# Razz_control_board.net
KiCad netlist of a schematic drawn in EAGLE
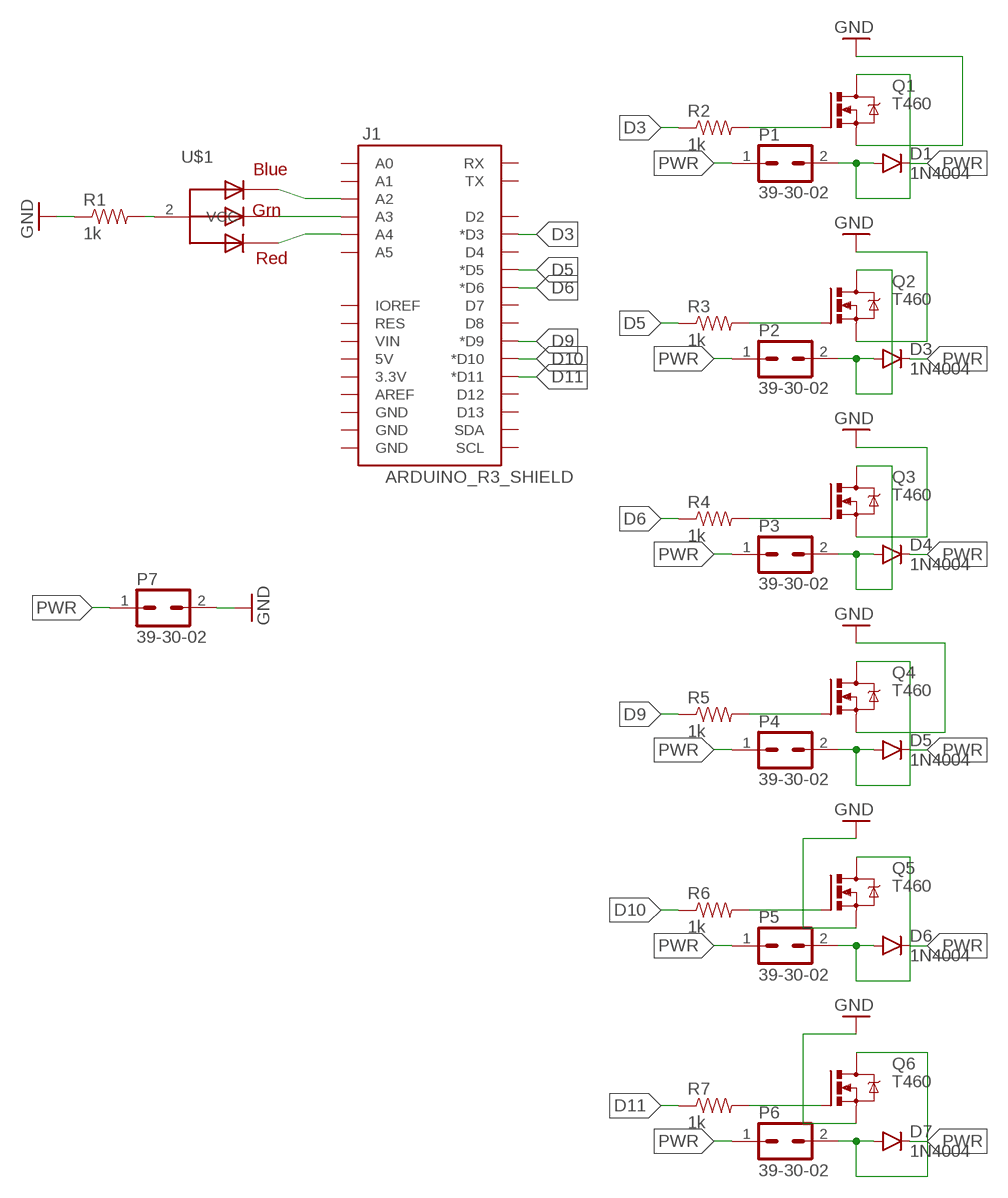
[diagram p0: schematic, sheet 1]

(export (version "E")
  (design (tool "Eeschema 10.0.6"))
  (components
    (comp (ref "D1")
      (value "1N4004")
      (footprint "eagle-import:DIODE-1N4001")
      (libsource (lib "eagle-import") (part "DIODEPTH"))
    )
    (comp (ref "D3")
      (value "1N4004")
      (footprint "eagle-import:DIODE-1N4001")
      (libsource (lib "eagle-import") (part "DIODEPTH"))
    )
    (comp (ref "D4")
      (value "1N4004")
      (footprint "eagle-import:DIODE-1N4001")
      (libsource (lib "eagle-import") (part "DIODEPTH"))
    )
    (comp (ref "D5")
      (value "1N4004")
      (footprint "eagle-import:DIODE-1N4001")
      (libsource (lib "eagle-import") (part "DIODEPTH"))
    )
    (comp (ref "D6")
      (value "1N4004")
      (footprint "eagle-import:DIODE-1N4001")
      (libsource (lib "eagle-import") (part "DIODEPTH"))
    )
    (comp (ref "D7")
      (value "1N4004")
      (footprint "eagle-import:DIODE-1N4001")
      (libsource (lib "eagle-import") (part "DIODEPTH"))
    )
    (comp (ref "J1")
      (value "ARDUINO_R3_SHIELD")
      (footprint "eagle-import:UNO_R3_SHIELD")
      (libsource (lib "eagle-import") (part "ARDUINO_R3_SHIELD"))
    )
    (comp (ref "P1")
      (value "39-30-02")
      (footprint "eagle-import:39-30-_02_")
      (libsource (lib "eagle-import") (part "39-30-?02?"))
    )
    (comp (ref "P2")
      (value "39-30-02")
      (footprint "eagle-import:39-30-_02_")
      (libsource (lib "eagle-import") (part "39-30-?02?"))
    )
    (comp (ref "P3")
      (value "39-30-02")
      (footprint "eagle-import:39-30-_02_")
      (libsource (lib "eagle-import") (part "39-30-?02?"))
    )
    (comp (ref "P4")
      (value "39-30-02")
      (footprint "eagle-import:39-30-_02_")
      (libsource (lib "eagle-import") (part "39-30-?02?"))
    )
    (comp (ref "P5")
      (value "39-30-02")
      (footprint "eagle-import:39-30-_02_")
      (libsource (lib "eagle-import") (part "39-30-?02?"))
    )
    (comp (ref "P6")
      (value "39-30-02")
      (footprint "eagle-import:39-30-_02_")
      (libsource (lib "eagle-import") (part "39-30-?02?"))
    )
    (comp (ref "P7")
      (value "39-30-02")
      (footprint "eagle-import:39-30-_02_")
      (libsource (lib "eagle-import") (part "39-30-?02?"))
    )
    (comp (ref "Q1")
      (value "T460")
      (footprint "eagle-import:TO220BV")
      (libsource (lib "eagle-import") (part "IRF540"))
    )
    (comp (ref "Q2")
      (value "T460")
      (footprint "eagle-import:TO220BV")
      (libsource (lib "eagle-import") (part "IRF540"))
    )
    (comp (ref "Q3")
      (value "T460")
      (footprint "eagle-import:TO220BV")
      (libsource (lib "eagle-import") (part "IRF540"))
    )
    (comp (ref "Q4")
      (value "T460")
      (footprint "eagle-import:TO220BV")
      (libsource (lib "eagle-import") (part "IRF540"))
    )
    (comp (ref "Q5")
      (value "T460")
      (footprint "eagle-import:TO220BV")
      (libsource (lib "eagle-import") (part "IRF540"))
    )
    (comp (ref "Q6")
      (value "T460")
      (footprint "eagle-import:TO220BV")
      (libsource (lib "eagle-import") (part "IRF540"))
    )
    (comp (ref "R1")
      (value "1k")
      (footprint "eagle-import:AXIAL-0.3EZ")
      (libsource (lib "eagle-import") (part "RESISTOREZ"))
    )
    (comp (ref "R2")
      (value "1k")
      (footprint "eagle-import:AXIAL-0.3EZ")
      (libsource (lib "eagle-import") (part "RESISTOREZ"))
    )
    (comp (ref "R3")
      (value "1k")
      (footprint "eagle-import:AXIAL-0.3EZ")
      (libsource (lib "eagle-import") (part "RESISTOREZ"))
    )
    (comp (ref "R4")
      (value "1k")
      (footprint "eagle-import:AXIAL-0.3EZ")
      (libsource (lib "eagle-import") (part "RESISTOREZ"))
    )
    (comp (ref "R5")
      (value "1k")
      (footprint "eagle-import:AXIAL-0.3EZ")
      (libsource (lib "eagle-import") (part "RESISTOREZ"))
    )
    (comp (ref "R6")
      (value "1k")
      (footprint "eagle-import:AXIAL-0.3EZ")
      (libsource (lib "eagle-import") (part "RESISTOREZ"))
    )
    (comp (ref "R7")
      (value "1k")
      (footprint "eagle-import:AXIAL-0.3EZ")
      (libsource (lib "eagle-import") (part "RESISTOREZ"))
    )
    (comp (ref "U$1")
      (value "RGBLED_CA")
      (footprint "eagle-import:LED5MMRGB")
      (libsource (lib "eagle-import") (part "RGBLED_CA"))
    )
  )
  (nets
    (net (code "1") (name "D3") (class "Default")
      (node (ref "J1") (pin "D3") (pinfunction "*D3_D3") (pintype "bidirectional"))
      (node (ref "R2") (pin "P$1") (pinfunction "1_P$1") (pintype "passive"))
    )
    (net (code "2") (name "D5") (class "Default")
      (node (ref "J1") (pin "D5") (pinfunction "*D5_D5") (pintype "bidirectional"))
      (node (ref "R3") (pin "P$1") (pinfunction "1_P$1") (pintype "passive"))
    )
    (net (code "3") (name "D6") (class "Default")
      (node (ref "J1") (pin "D6") (pinfunction "*D6_D6") (pintype "bidirectional"))
      (node (ref "R4") (pin "P$1") (pinfunction "1_P$1") (pintype "passive"))
    )
    (net (code "4") (name "D9") (class "Default")
      (node (ref "J1") (pin "D9") (pinfunction "*D9_D9") (pintype "bidirectional"))
      (node (ref "R5") (pin "P$1") (pinfunction "1_P$1") (pintype "passive"))
    )
    (net (code "5") (name "D10") (class "Default")
      (node (ref "J1") (pin "D10") (pinfunction "*D10_D10") (pintype "bidirectional"))
      (node (ref "R6") (pin "P$1") (pinfunction "1_P$1") (pintype "passive"))
    )
    (net (code "6") (name "D11") (class "Default")
      (node (ref "J1") (pin "D11") (pinfunction "*D11_D11") (pintype "bidirectional"))
      (node (ref "R7") (pin "P$1") (pinfunction "1_P$1") (pintype "passive"))
    )
    (net (code "7") (name "GND") (class "Default")
      (node (ref "P7") (pin "2") (pinfunction "2_2") (pintype "passive"))
      (node (ref "Q1") (pin "S") (pinfunction "S_S") (pintype "passive"))
      (node (ref "Q2") (pin "S") (pinfunction "S_S") (pintype "passive"))
      (node (ref "Q3") (pin "S") (pinfunction "S_S") (pintype "passive"))
      (node (ref "Q4") (pin "S") (pinfunction "S_S") (pintype "passive"))
      (node (ref "Q5") (pin "S") (pinfunction "S_S") (pintype "passive"))
      (node (ref "Q6") (pin "S") (pinfunction "S_S") (pintype "passive"))
      (node (ref "R1") (pin "P$1") (pinfunction "1_P$1") (pintype "passive"))
    )
    (net (code "8") (name "Net-(D1-PadA)") (class "Default")
      (node (ref "D1") (pin "A") (pinfunction "A_A") (pintype "passive"))
      (node (ref "P1") (pin "2") (pinfunction "2_2") (pintype "passive"))
      (node (ref "Q1") (pin "D") (pinfunction "D_D") (pintype "passive"))
    )
    (net (code "9") (name "Net-(D3-PadA)") (class "Default")
      (node (ref "D3") (pin "A") (pinfunction "A_A") (pintype "passive"))
      (node (ref "P2") (pin "2") (pinfunction "2_2") (pintype "passive"))
      (node (ref "Q2") (pin "D") (pinfunction "D_D") (pintype "passive"))
    )
    (net (code "10") (name "Net-(D4-PadA)") (class "Default")
      (node (ref "D4") (pin "A") (pinfunction "A_A") (pintype "passive"))
      (node (ref "P3") (pin "2") (pinfunction "2_2") (pintype "passive"))
      (node (ref "Q3") (pin "D") (pinfunction "D_D") (pintype "passive"))
    )
    (net (code "11") (name "Net-(D5-PadA)") (class "Default")
      (node (ref "D5") (pin "A") (pinfunction "A_A") (pintype "passive"))
      (node (ref "P4") (pin "2") (pinfunction "2_2") (pintype "passive"))
      (node (ref "Q4") (pin "D") (pinfunction "D_D") (pintype "passive"))
    )
    (net (code "12") (name "Net-(D6-PadA)") (class "Default")
      (node (ref "D6") (pin "A") (pinfunction "A_A") (pintype "passive"))
      (node (ref "P5") (pin "2") (pinfunction "2_2") (pintype "passive"))
      (node (ref "Q5") (pin "D") (pinfunction "D_D") (pintype "passive"))
    )
    (net (code "13") (name "Net-(D7-PadA)") (class "Default")
      (node (ref "D7") (pin "A") (pinfunction "A_A") (pintype "passive"))
      (node (ref "P6") (pin "2") (pinfunction "2_2") (pintype "passive"))
      (node (ref "Q6") (pin "D") (pinfunction "D_D") (pintype "passive"))
    )
    (net (code "14") (name "Net-(R1-2)") (class "Default")
      (node (ref "R1") (pin "P$2") (pinfunction "2_P$2") (pintype "passive"))
      (node (ref "U$1") (pin "2") (pinfunction "VCC_2") (pintype "bidirectional"))
    )
    (net (code "15") (name "Net-(R2-2)") (class "Default")
      (node (ref "Q1") (pin "G") (pinfunction "G_G") (pintype "passive"))
      (node (ref "R2") (pin "P$2") (pinfunction "2_P$2") (pintype "passive"))
    )
    (net (code "16") (name "Net-(R3-2)") (class "Default")
      (node (ref "Q2") (pin "G") (pinfunction "G_G") (pintype "passive"))
      (node (ref "R3") (pin "P$2") (pinfunction "2_P$2") (pintype "passive"))
    )
    (net (code "17") (name "Net-(R4-2)") (class "Default")
      (node (ref "Q3") (pin "G") (pinfunction "G_G") (pintype "passive"))
      (node (ref "R4") (pin "P$2") (pinfunction "2_P$2") (pintype "passive"))
    )
    (net (code "18") (name "Net-(R5-2)") (class "Default")
      (node (ref "Q4") (pin "G") (pinfunction "G_G") (pintype "passive"))
      (node (ref "R5") (pin "P$2") (pinfunction "2_P$2") (pintype "passive"))
    )
    (net (code "19") (name "Net-(R6-2)") (class "Default")
      (node (ref "Q5") (pin "G") (pinfunction "G_G") (pintype "passive"))
      (node (ref "R6") (pin "P$2") (pinfunction "2_P$2") (pintype "passive"))
    )
    (net (code "20") (name "Net-(R7-2)") (class "Default")
      (node (ref "Q6") (pin "G") (pinfunction "G_G") (pintype "passive"))
      (node (ref "R7") (pin "P$2") (pinfunction "2_P$2") (pintype "passive"))
    )
    (net (code "21") (name "Net-(U$1-BLUE)") (class "Default")
      (node (ref "J1") (pin "A2") (pinfunction "A2_A2") (pintype "bidirectional"))
      (node (ref "U$1") (pin "4") (pinfunction "BLUE_4") (pintype "bidirectional"))
    )
    (net (code "22") (name "Net-(U$1-GREEN)") (class "Default")
      (node (ref "J1") (pin "A3") (pinfunction "A3_A3") (pintype "bidirectional"))
      (node (ref "U$1") (pin "3") (pinfunction "GREEN_3") (pintype "bidirectional"))
    )
    (net (code "23") (name "Net-(U$1-RED)") (class "Default")
      (node (ref "J1") (pin "A4") (pinfunction "A4_A4") (pintype "bidirectional"))
      (node (ref "U$1") (pin "1") (pinfunction "RED_1") (pintype "bidirectional"))
    )
    (net (code "24") (name "PWR") (class "Default")
      (node (ref "D1") (pin "C") (pinfunction "C_C") (pintype "passive"))
      (node (ref "D3") (pin "C") (pinfunction "C_C") (pintype "passive"))
      (node (ref "D4") (pin "C") (pinfunction "C_C") (pintype "passive"))
      (node (ref "D5") (pin "C") (pinfunction "C_C") (pintype "passive"))
      (node (ref "D6") (pin "C") (pinfunction "C_C") (pintype "passive"))
      (node (ref "D7") (pin "C") (pinfunction "C_C") (pintype "passive"))
      (node (ref "P1") (pin "1") (pinfunction "1_1") (pintype "passive"))
      (node (ref "P2") (pin "1") (pinfunction "1_1") (pintype "passive"))
      (node (ref "P3") (pin "1") (pinfunction "1_1") (pintype "passive"))
      (node (ref "P4") (pin "1") (pinfunction "1_1") (pintype "passive"))
      (node (ref "P5") (pin "1") (pinfunction "1_1") (pintype "passive"))
      (node (ref "P6") (pin "1") (pinfunction "1_1") (pintype "passive"))
      (node (ref "P7") (pin "1") (pinfunction "1_1") (pintype "passive"))
    )
    (net (code "25") (name "unconnected-(J1-GND-PadGND@0)") (class "Default")
      (node (ref "J1") (pin "GND@0") (pinfunction "GND_GND@0") (pintype "bidirectional"))
    )
    (net (code "26") (name "unconnected-(J1-GND-PadGND@1)") (class "Default")
      (node (ref "J1") (pin "GND@1") (pinfunction "GND_GND@1") (pintype "bidirectional"))
    )
    (net (code "27") (name "unconnected-(J1-GND-PadGND@2)") (class "Default")
      (node (ref "J1") (pin "GND@2") (pinfunction "GND_GND@2") (pintype "bidirectional"))
    )
    (net (code "28") (name "unconnected-(J1-Pad3.3V)") (class "Default")
      (node (ref "J1") (pin "3.3V") (pinfunction "3.3V_3.3V") (pintype "bidirectional"))
    )
    (net (code "29") (name "unconnected-(J1-Pad5V)") (class "Default")
      (node (ref "J1") (pin "5V") (pinfunction "5V_5V") (pintype "bidirectional"))
    )
    (net (code "30") (name "unconnected-(J1-PadA0)") (class "Default")
      (node (ref "J1") (pin "A0") (pinfunction "A0_A0") (pintype "bidirectional"))
    )
    (net (code "31") (name "unconnected-(J1-PadA1)") (class "Default")
      (node (ref "J1") (pin "A1") (pinfunction "A1_A1") (pintype "bidirectional"))
    )
    (net (code "32") (name "unconnected-(J1-PadA5)") (class "Default")
      (node (ref "J1") (pin "A5") (pinfunction "A5_A5") (pintype "bidirectional"))
    )
    (net (code "33") (name "unconnected-(J1-PadAREF)") (class "Default")
      (node (ref "J1") (pin "AREF") (pinfunction "AREF_AREF") (pintype "bidirectional"))
    )
    (net (code "34") (name "unconnected-(J1-PadD2)") (class "Default")
      (node (ref "J1") (pin "D2") (pinfunction "D2_D2") (pintype "bidirectional"))
    )
    (net (code "35") (name "unconnected-(J1-PadD4)") (class "Default")
      (node (ref "J1") (pin "D4") (pinfunction "D4_D4") (pintype "bidirectional"))
    )
    (net (code "36") (name "unconnected-(J1-PadD7)") (class "Default")
      (node (ref "J1") (pin "D7") (pinfunction "D7_D7") (pintype "bidirectional"))
    )
    (net (code "37") (name "unconnected-(J1-PadD8)") (class "Default")
      (node (ref "J1") (pin "D8") (pinfunction "D8_D8") (pintype "bidirectional"))
    )
    (net (code "38") (name "unconnected-(J1-PadD12)") (class "Default")
      (node (ref "J1") (pin "D12") (pinfunction "D12_D12") (pintype "bidirectional"))
    )
    (net (code "39") (name "unconnected-(J1-PadD13)") (class "Default")
      (node (ref "J1") (pin "D13") (pinfunction "D13_D13") (pintype "bidirectional"))
    )
    (net (code "40") (name "unconnected-(J1-PadIOREF)") (class "Default")
      (node (ref "J1") (pin "IOREF") (pinfunction "IOREF_IOREF") (pintype "bidirectional"))
    )
    (net (code "41") (name "unconnected-(J1-PadRES)") (class "Default")
      (node (ref "J1") (pin "RES") (pinfunction "RES_RES") (pintype "bidirectional"))
    )
    (net (code "42") (name "unconnected-(J1-PadRX)") (class "Default")
      (node (ref "J1") (pin "RX") (pinfunction "RX_RX") (pintype "bidirectional"))
    )
    (net (code "43") (name "unconnected-(J1-PadSCL)") (class "Default")
      (node (ref "J1") (pin "SCL") (pinfunction "SCL_SCL") (pintype "bidirectional"))
    )
    (net (code "44") (name "unconnected-(J1-PadSDA)") (class "Default")
      (node (ref "J1") (pin "SDA") (pinfunction "SDA_SDA") (pintype "bidirectional"))
    )
    (net (code "45") (name "unconnected-(J1-PadTX)") (class "Default")
      (node (ref "J1") (pin "TX") (pinfunction "TX_TX") (pintype "bidirectional"))
    )
    (net (code "46") (name "unconnected-(J1-PadVIN)") (class "Default")
      (node (ref "J1") (pin "VIN") (pinfunction "VIN_VIN") (pintype "bidirectional"))
    )
  )
)
